# SHDN-S07-V00-CAN.net
KiCad netlist of a schematic drawn in Altium Designer
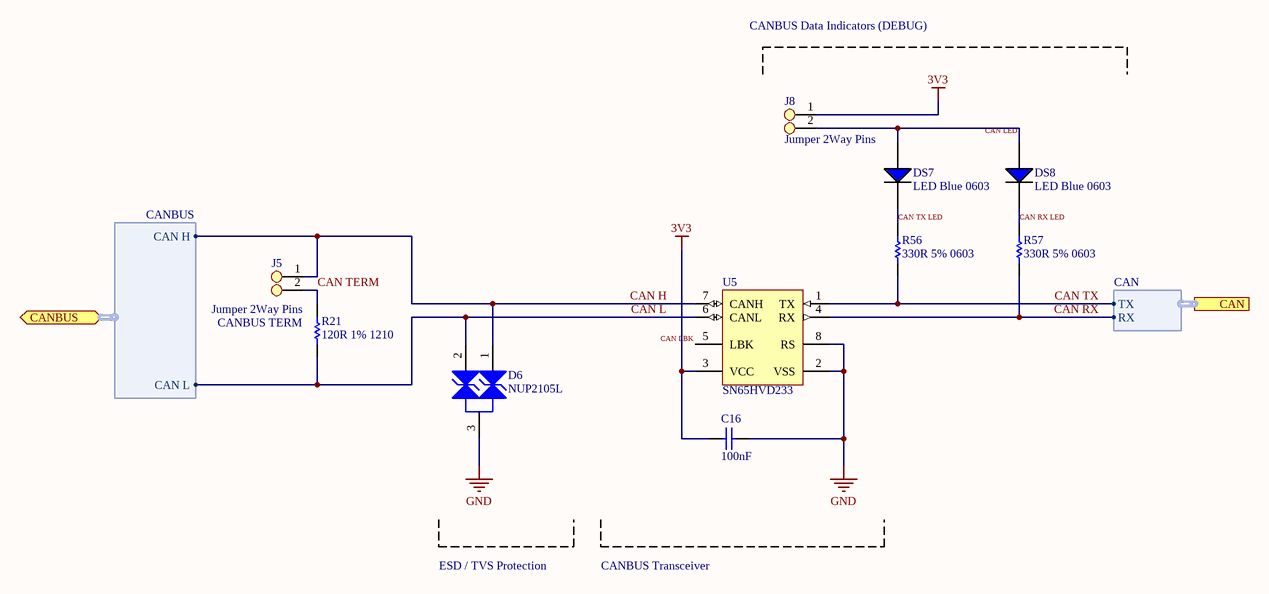
[diagram p0: SHDN-S07-V00-CAN.SchDoc]

(export (version "E")
  (design (tool "Eeschema 10.0.6"))
  (components
    (comp (ref "C16")
      (value "100nF")
      (footprint "Cap_Ceramic_0603")
      (description "Capacitor, Ceramic, SMD, 100nF, 50V, 5%, X7R, 0603")
      (libsource (lib "StandardCapacitors") (part "100nF 50V 5% X7R 0603"))
    )
    (comp (ref "D6")
      (value "NUP2105L")
      (footprint "NUP2105L")
      (libsource (lib "QUTMS_CANLibrary") (part "NUP2105L"))
    )
    (comp (ref "DS7")
      (value "LED Blue 0603")
      (footprint "LED BLUE 0603")
      (libsource (lib "QUTMS_LEDLibrary") (part "LED BLUE 0603"))
    )
    (comp (ref "DS8")
      (value "LED Blue 0603")
      (footprint "LED BLUE 0603")
      (libsource (lib "QUTMS_LEDLibrary") (part "LED BLUE 0603"))
    )
    (comp (ref "J5")
      (value "Jumper 2Way Pins")
      (footprint "Jumper_2Way_Pin")
      (description "Jumper 2Way Side Pins")
      (libsource (lib "QUTMS_JumperLibrary") (part "Jumper 2Way Side Pins"))
    )
    (comp (ref "J8")
      (value "Jumper 2Way Pins")
      (footprint "Jumper_2Way_Pin")
      (description "Jumper 2Way Side Pins")
      (libsource (lib "QUTMS_JumperLibrary") (part "Jumper 2Way Side Pins"))
    )
    (comp (ref "R21")
      (value "120R 1% 1210")
      (footprint "Res_ThinFilm_1210")
      (description "Resistor, SMD, 120R, 0.25W, 1%, 1210")
      (libsource (lib "StandardResistors") (part "120R 1% 1210"))
    )
    (comp (ref "R56")
      (value "330R 5% 0603")
      (footprint "Res_ThinFilm_0603")
      (description "Resistor, SMD, 330R, 0.1W, 5%, 0603")
      (libsource (lib "StandardResistors") (part "330R 5% 0603"))
    )
    (comp (ref "R57")
      (value "330R 5% 0603")
      (footprint "Res_ThinFilm_0603")
      (description "Resistor, SMD, 330R, 0.1W, 5%, 0603")
      (libsource (lib "StandardResistors") (part "330R 5% 0603"))
    )
    (comp (ref "U5")
      (value "SN65HVD233")
      (footprint "SN65HVD233DR")
      (libsource (lib "QUTMS_CANLibrary") (part "SN65HVD233"))
    )
  )
  (nets
    (net (code "3") (name "/CAN H") (class "Default")
      (node (ref "D6") (pin "1") (pinfunction "1_1") (pintype "passive"))
      (node (ref "J5") (pin "1") (pinfunction "1_1") (pintype "passive"))
      (node (ref "U5") (pin "7") (pinfunction "CANH_7") (pintype "bidirectional"))
    )
    (net (code "4") (name "/CAN L") (class "Default")
      (node (ref "D6") (pin "2") (pinfunction "2_2") (pintype "passive"))
      (node (ref "R21") (pin "1") (pinfunction "1_1") (pintype "passive"))
      (node (ref "U5") (pin "6") (pinfunction "CANL_6") (pintype "bidirectional"))
    )
    (net (code "5") (name "/CAN LBK") (class "Default")
      (node (ref "U5") (pin "5") (pinfunction "LBK_5") (pintype "passive"))
    )
    (net (code "6") (name "/CAN LED") (class "Default")
      (node (ref "DS7") (pin "1") (pinfunction "A_1") (pintype "passive"))
      (node (ref "DS8") (pin "1") (pinfunction "A_1") (pintype "passive"))
      (node (ref "J8") (pin "2") (pinfunction "2_2") (pintype "passive"))
    )
    (net (code "7") (name "/CAN RX") (class "Default")
      (node (ref "R57") (pin "1") (pinfunction "1_1") (pintype "passive"))
      (node (ref "U5") (pin "4") (pinfunction "RX_4") (pintype "output"))
    )
    (net (code "8") (name "/CAN RX LED") (class "Default")
      (node (ref "DS8") (pin "2") (pinfunction "C_2") (pintype "passive"))
      (node (ref "R57") (pin "2") (pinfunction "2_2") (pintype "passive"))
    )
    (net (code "9") (name "/CAN TERM") (class "Default")
      (node (ref "J5") (pin "2") (pinfunction "2_2") (pintype "passive"))
      (node (ref "R21") (pin "2") (pinfunction "2_2") (pintype "passive"))
    )
    (net (code "10") (name "/CAN TX") (class "Default")
      (node (ref "R56") (pin "1") (pinfunction "1_1") (pintype "passive"))
      (node (ref "U5") (pin "1") (pinfunction "TX_1") (pintype "input"))
    )
    (net (code "11") (name "/CAN TX LED") (class "Default")
      (node (ref "DS7") (pin "2") (pinfunction "C_2") (pintype "passive"))
      (node (ref "R56") (pin "2") (pinfunction "2_2") (pintype "passive"))
    )
    (net (code "14") (name "3V3") (class "Default")
      (node (ref "C16") (pin "2") (pinfunction "2_2") (pintype "passive"))
      (node (ref "J8") (pin "1") (pinfunction "1_1") (pintype "passive"))
      (node (ref "U5") (pin "3") (pinfunction "VCC_3") (pintype "passive"))
    )
    (net (code "15") (name "GND") (class "Default")
      (node (ref "C16") (pin "1") (pinfunction "1_1") (pintype "passive"))
      (node (ref "D6") (pin "3") (pinfunction "3_3") (pintype "passive"))
      (node (ref "U5") (pin "2") (pinfunction "VSS_2") (pintype "passive"))
      (node (ref "U5") (pin "8") (pinfunction "RS_8") (pintype "passive"))
    )
  )
)
